# RotaryEncoder1.net
KiCad netlist of a schematic drawn in EAGLE
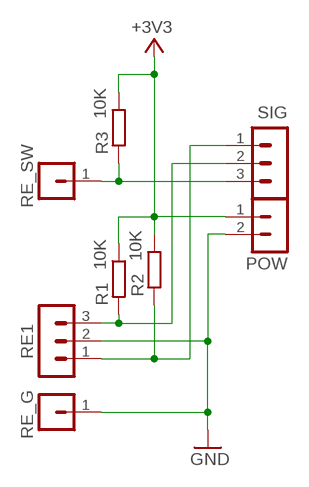
[diagram p0: schematic, sheet 1]

(export (version "E")
  (design (tool "Eeschema 10.0.6"))
  (components
    (comp (ref "POW")
      (value "PINHEAD-MA02-1")
      (footprint "eagle-import:PINHEAD-MA02-1")
      (libsource (lib "eagle-import") (part "PINHEAD-MA02-1"))
    )
    (comp (ref "R1")
      (value "10K")
      (footprint "eagle-import:0204_5")
      (libsource (lib "eagle-import") (part "R-EU_0204/5"))
    )
    (comp (ref "R2")
      (value "10K")
      (footprint "eagle-import:0204_5")
      (libsource (lib "eagle-import") (part "R-EU_0204/5"))
    )
    (comp (ref "R3")
      (value "10K")
      (footprint "eagle-import:0204_5")
      (libsource (lib "eagle-import") (part "R-EU_0204/5"))
    )
    (comp (ref "RE1")
      (value "PINHEAD-MA03-1")
      (footprint "eagle-import:PINHEAD-MA03-1")
      (libsource (lib "eagle-import") (part "PINHEAD-MA03-1"))
    )
    (comp (ref "RE_G")
      (value "PINHEAD-MA01-1")
      (footprint "eagle-import:PINHEAD-MA01-1")
      (libsource (lib "eagle-import") (part "PINHEAD-MA01-1"))
    )
    (comp (ref "RE_SW")
      (value "PINHEAD-MA01-1")
      (footprint "eagle-import:PINHEAD-MA01-1")
      (libsource (lib "eagle-import") (part "PINHEAD-MA01-1"))
    )
    (comp (ref "SIG")
      (value "PINHEAD-MA03-1")
      (footprint "eagle-import:PINHEAD-MA03-1")
      (libsource (lib "eagle-import") (part "PINHEAD-MA03-1"))
    )
  )
  (nets
    (net (code "1") (name "+3V3") (class "Default")
      (node (ref "POW") (pin "1") (pinfunction "1_1") (pintype "passive"))
      (node (ref "R1") (pin "1") (pinfunction "1_1") (pintype "passive"))
      (node (ref "R2") (pin "2") (pinfunction "2_2") (pintype "passive"))
      (node (ref "R3") (pin "1") (pinfunction "1_1") (pintype "passive"))
    )
    (net (code "2") (name "GND") (class "Default")
      (node (ref "POW") (pin "2") (pinfunction "2_2") (pintype "passive"))
      (node (ref "RE1") (pin "2") (pinfunction "2_2") (pintype "passive"))
      (node (ref "RE_G") (pin "1") (pinfunction "1_1") (pintype "passive"))
    )
    (net (code "3") (name "Net-(R1-Pad2)") (class "Default")
      (node (ref "R1") (pin "2") (pinfunction "2_2") (pintype "passive"))
      (node (ref "RE1") (pin "3") (pinfunction "3_3") (pintype "passive"))
      (node (ref "SIG") (pin "2") (pinfunction "2_2") (pintype "passive"))
    )
    (net (code "4") (name "Net-(R2-Pad1)") (class "Default")
      (node (ref "R2") (pin "1") (pinfunction "1_1") (pintype "passive"))
      (node (ref "RE1") (pin "1") (pinfunction "1_1") (pintype "passive"))
      (node (ref "SIG") (pin "1") (pinfunction "1_1") (pintype "passive"))
    )
    (net (code "5") (name "Net-(R3-Pad2)") (class "Default")
      (node (ref "R3") (pin "2") (pinfunction "2_2") (pintype "passive"))
      (node (ref "RE_SW") (pin "1") (pinfunction "1_1") (pintype "passive"))
      (node (ref "SIG") (pin "3") (pinfunction "3_3") (pintype "passive"))
    )
  )
)
